# Adafruit_BME680_Original.net
KiCad netlist of a schematic drawn in EAGLE
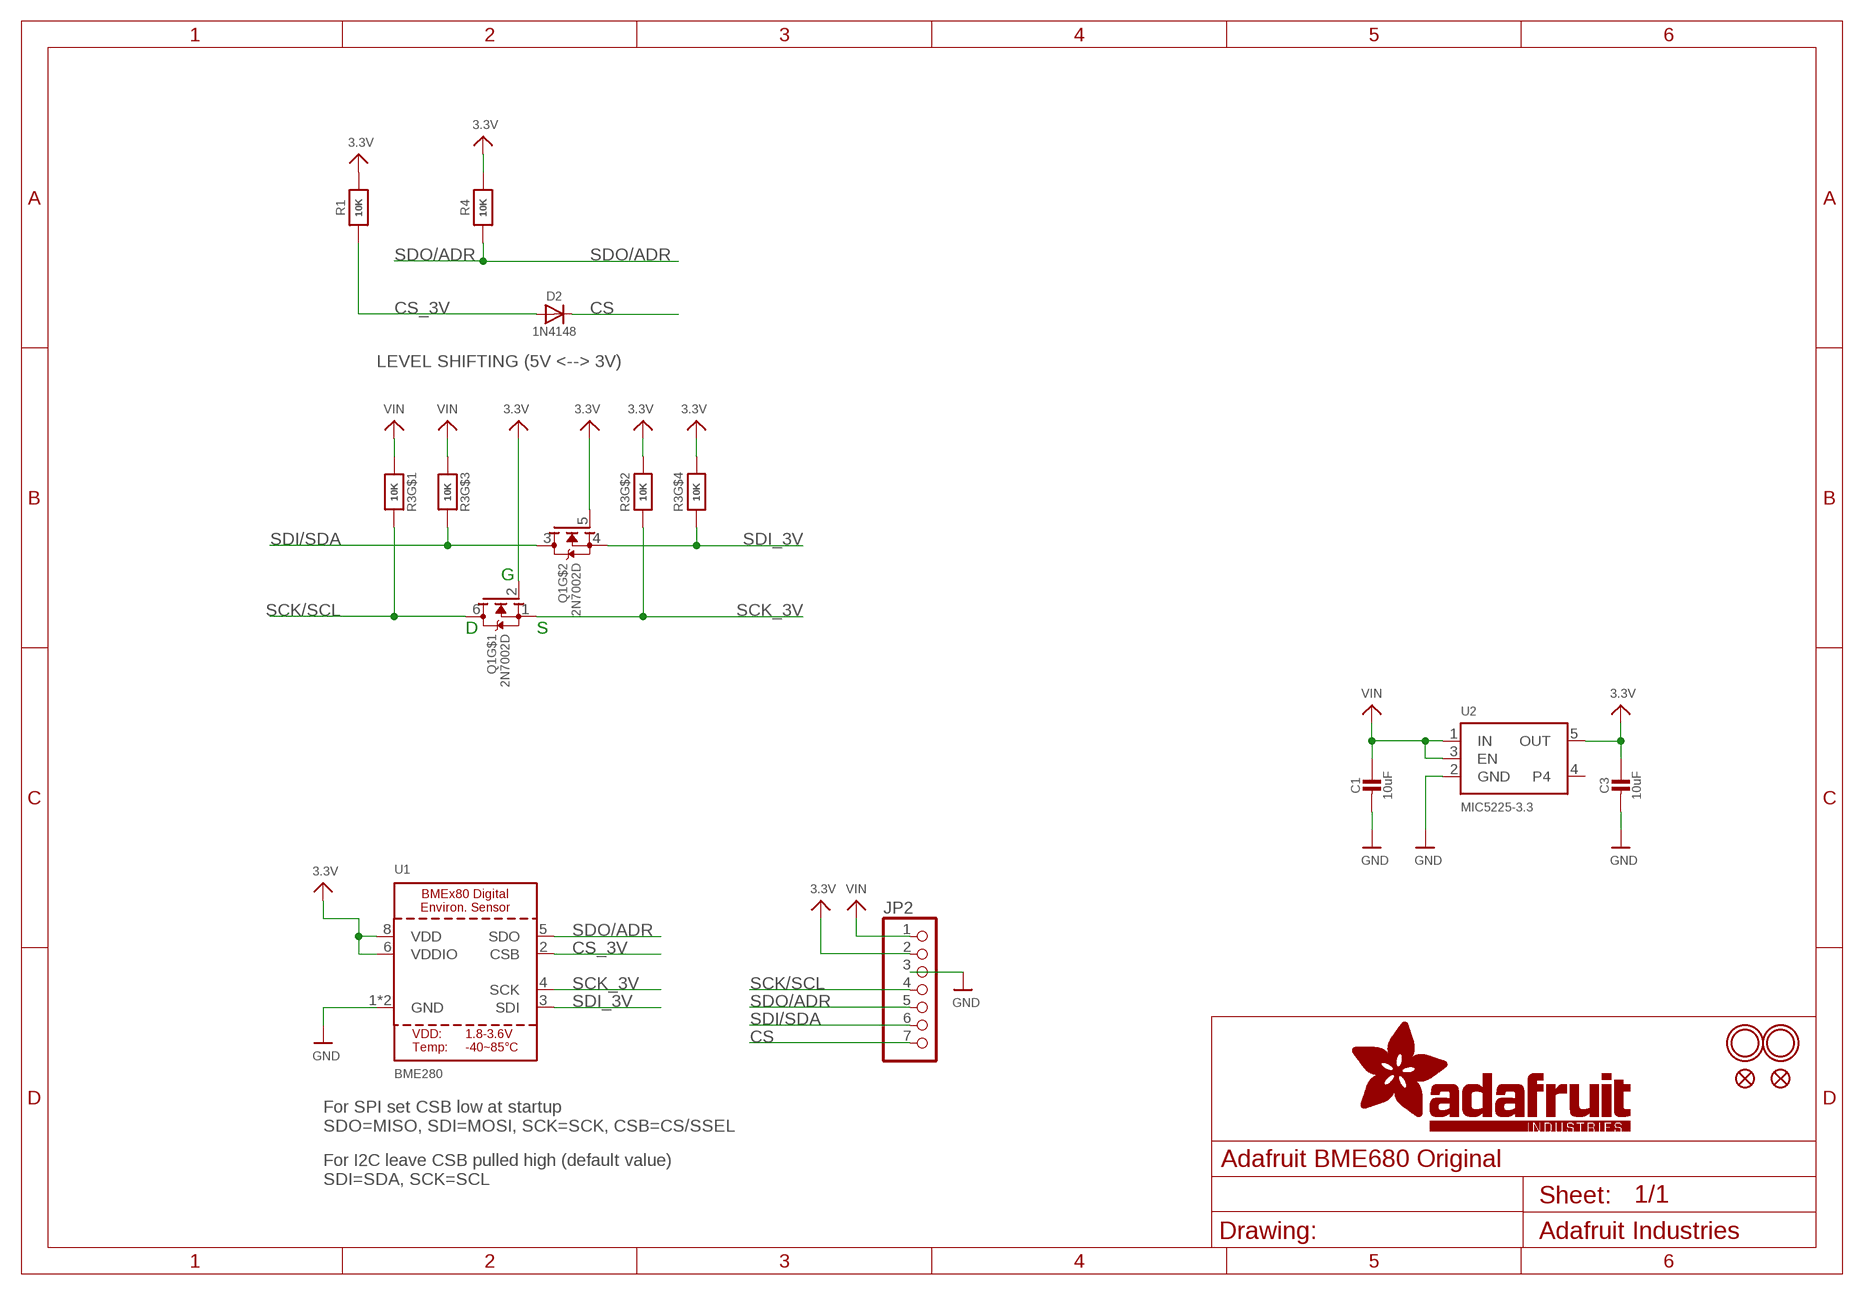
[diagram p0: schematic, sheet 1]

(export (version "E")
  (design (tool "Eeschema 10.0.6"))
  (components
    (comp (ref "C1")
      (value "10uF")
      (footprint "eagle-import:0805-NO")
      (libsource (lib "eagle-import") (part "CAP_CERAMIC0805-NOOUTLINE"))
    )
    (comp (ref "C3")
      (value "10uF")
      (footprint "eagle-import:0805-NO")
      (libsource (lib "eagle-import") (part "CAP_CERAMIC0805-NOOUTLINE"))
    )
    (comp (ref "D2")
      (value "1N4148")
      (footprint "eagle-import:SOD-323")
      (libsource (lib "eagle-import") (part "DIODESOD-323"))
    )
    (comp (ref "JP2")
      (value "HEADER-1X770MIL")
      (footprint "eagle-import:1X07_ROUND_70")
      (libsource (lib "eagle-import") (part "HEADER-1X770MIL"))
    )
    (comp (ref "Q1")
      (value "2N7002D")
      (footprint "eagle-import:SOT363")
      (libsource (lib "eagle-import") (part "MOSFET-N_DUAL"))
    )
    (comp (ref "R1")
      (value "10K")
      (footprint "eagle-import:0603-NO")
      (libsource (lib "eagle-import") (part "RESISTOR_0603_NOOUT"))
    )
    (comp (ref "R3")
      (value "10K")
      (footprint "eagle-import:RESPACK_4X0603")
      (libsource (lib "eagle-import") (part "RESISTOR_4PACK"))
    )
    (comp (ref "R4")
      (value "10K")
      (footprint "eagle-import:0603-NO")
      (libsource (lib "eagle-import") (part "RESISTOR_0603_NOOUT"))
    )
    (comp (ref "U$5")
      (value "FIDUCIAL_1MM")
      (footprint "eagle-import:FIDUCIAL_1MM")
      (libsource (lib "eagle-import") (part "FIDUCIAL_1MM"))
    )
    (comp (ref "U$7")
      (value "MOUNTINGHOLE2.0")
      (footprint "eagle-import:MOUNTINGHOLE_2.0_PLATED")
      (libsource (lib "eagle-import") (part "MOUNTINGHOLE2.0"))
    )
    (comp (ref "U$8")
      (value "MOUNTINGHOLE2.0")
      (footprint "eagle-import:MOUNTINGHOLE_2.0_PLATED")
      (libsource (lib "eagle-import") (part "MOUNTINGHOLE2.0"))
    )
    (comp (ref "U$15")
      (value "FIDUCIAL_1MM")
      (footprint "eagle-import:FIDUCIAL_1MM")
      (libsource (lib "eagle-import") (part "FIDUCIAL_1MM"))
    )
    (comp (ref "U1")
      (value "BME280")
      (footprint "eagle-import:BME680")
      (libsource (lib "eagle-import") (part "BME680"))
    )
    (comp (ref "U2")
      (value "MIC5225-3.3")
      (footprint "eagle-import:SOT23-5")
      (libsource (lib "eagle-import") (part "VREG_SOT23-5"))
    )
  )
  (nets
    (net (code "1") (name "/CS") (class "Default")
      (node (ref "D2") (pin "C") (pinfunction "C_C") (pintype "passive"))
      (node (ref "JP2") (pin "7") (pinfunction "7_7") (pintype "passive"))
    )
    (net (code "2") (name "/CS_3V") (class "Default")
      (node (ref "D2") (pin "A") (pinfunction "A_A") (pintype "passive"))
      (node (ref "R1") (pin "1") (pinfunction "1_1") (pintype "passive"))
      (node (ref "U1") (pin "2") (pinfunction "CSB_2") (pintype "input"))
    )
    (net (code "3") (name "/SCK_3V") (class "Default")
      (node (ref "Q1") (pin "1") (pinfunction "S_1") (pintype "bidirectional"))
      (node (ref "R3") (pin "7") (pinfunction "2_7") (pintype "passive"))
      (node (ref "U1") (pin "4") (pinfunction "SCK_4") (pintype "input"))
    )
    (net (code "4") (name "/SCK{slash}SCL") (class "Default")
      (node (ref "JP2") (pin "4") (pinfunction "4_4") (pintype "passive"))
      (node (ref "Q1") (pin "6") (pinfunction "D_6") (pintype "bidirectional"))
      (node (ref "R3") (pin "8") (pinfunction "2_8") (pintype "passive"))
    )
    (net (code "5") (name "/SDI_3V") (class "Default")
      (node (ref "Q1") (pin "4") (pinfunction "S_4") (pintype "bidirectional"))
      (node (ref "R3") (pin "5") (pinfunction "2_5") (pintype "passive"))
      (node (ref "U1") (pin "3") (pinfunction "SDI_3") (pintype "input"))
    )
    (net (code "6") (name "/SDI{slash}SDA") (class "Default")
      (node (ref "JP2") (pin "6") (pinfunction "6_6") (pintype "passive"))
      (node (ref "Q1") (pin "3") (pinfunction "D_3") (pintype "bidirectional"))
      (node (ref "R3") (pin "6") (pinfunction "2_6") (pintype "passive"))
    )
    (net (code "7") (name "/SDO{slash}ADR") (class "Default")
      (node (ref "JP2") (pin "5") (pinfunction "5_5") (pintype "passive"))
      (node (ref "R4") (pin "1") (pinfunction "1_1") (pintype "passive"))
      (node (ref "U1") (pin "5") (pinfunction "SDO_5") (pintype "output"))
    )
    (net (code "8") (name "3.3V") (class "Default")
      (node (ref "C3") (pin "1") (pinfunction "1_1") (pintype "passive"))
      (node (ref "JP2") (pin "2") (pinfunction "2_2") (pintype "passive"))
      (node (ref "Q1") (pin "2") (pinfunction "G_2") (pintype "bidirectional"))
      (node (ref "Q1") (pin "5") (pinfunction "G_5") (pintype "bidirectional"))
      (node (ref "R1") (pin "2") (pinfunction "2_2") (pintype "passive"))
      (node (ref "R3") (pin "2") (pinfunction "1_2") (pintype "passive"))
      (node (ref "R3") (pin "4") (pinfunction "1_4") (pintype "passive"))
      (node (ref "R4") (pin "2") (pinfunction "2_2") (pintype "passive"))
      (node (ref "U1") (pin "6") (pinfunction "VDDIO_6") (pintype "power_in"))
      (node (ref "U1") (pin "8") (pinfunction "VDD_8") (pintype "power_in"))
      (node (ref "U2") (pin "5") (pinfunction "OUT_5") (pintype "power_in"))
    )
    (net (code "9") (name "GND") (class "Default")
      (node (ref "C1") (pin "2") (pinfunction "2_2") (pintype "passive"))
      (node (ref "C3") (pin "2") (pinfunction "2_2") (pintype "passive"))
      (node (ref "JP2") (pin "3") (pinfunction "3_3") (pintype "passive"))
      (node (ref "U1") (pin "1") (pinfunction "GND_1") (pintype "power_in"))
      (node (ref "U1") (pin "7") (pinfunction "GND_7") (pintype "power_in"))
      (node (ref "U2") (pin "2") (pinfunction "GND_2") (pintype "power_in"))
    )
    (net (code "10") (name "VIN") (class "Default")
      (node (ref "C1") (pin "1") (pinfunction "1_1") (pintype "passive"))
      (node (ref "JP2") (pin "1") (pinfunction "1_1") (pintype "passive"))
      (node (ref "R3") (pin "1") (pinfunction "1_1") (pintype "passive"))
      (node (ref "R3") (pin "3") (pinfunction "1_3") (pintype "passive"))
      (node (ref "U2") (pin "1") (pinfunction "IN_1") (pintype "power_in"))
      (node (ref "U2") (pin "3") (pinfunction "EN_3") (pintype "input"))
    )
    (net (code "11") (name "unconnected-(U2-P4-Pad4)") (class "Default")
      (node (ref "U2") (pin "4") (pinfunction "P4_4") (pintype "bidirectional"))
    )
  )
)
